# AD_Test.net
KiCad netlist of a schematic drawn in EAGLE
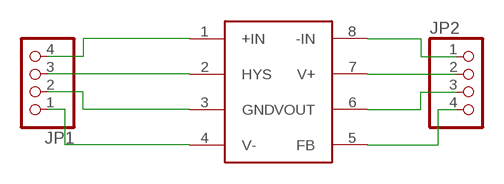
[diagram p0: schematic, sheet 1]

(export (version "E")
  (design (tool "Eeschema 10.0.6"))
  (components
    (comp (ref "JP1")
      (value "PINHD-1X4")
      (footprint "eagle-import:1X04")
      (libsource (lib "eagle-import") (part "PINHD-1X4"))
    )
    (comp (ref "JP2")
      (value "PINHD-1X4")
      (footprint "eagle-import:1X04")
      (libsource (lib "eagle-import") (part "PINHD-1X4"))
    )
    (comp (ref "U$1")
      (value "AD597ARZ")
      (footprint "eagle-import:SO8")
      (libsource (lib "eagle-import") (part "AD597ARZ"))
    )
  )
  (nets
    (net (code "1") (name "Net-(U$1-+IN)") (class "Default")
      (node (ref "JP1") (pin "4") (pinfunction "4_4") (pintype "passive"))
      (node (ref "U$1") (pin "1") (pinfunction "+IN_1") (pintype "bidirectional"))
    )
    (net (code "2") (name "Net-(U$1--IN)") (class "Default")
      (node (ref "JP2") (pin "1") (pinfunction "1_1") (pintype "passive"))
      (node (ref "U$1") (pin "8") (pinfunction "-IN_8") (pintype "bidirectional"))
    )
    (net (code "3") (name "Net-(U$1-FB)") (class "Default")
      (node (ref "JP2") (pin "4") (pinfunction "4_4") (pintype "passive"))
      (node (ref "U$1") (pin "5") (pinfunction "FB_5") (pintype "bidirectional"))
    )
    (net (code "4") (name "Net-(U$1-GND)") (class "Default")
      (node (ref "JP1") (pin "2") (pinfunction "2_2") (pintype "passive"))
      (node (ref "U$1") (pin "3") (pinfunction "GND_3") (pintype "bidirectional"))
    )
    (net (code "5") (name "Net-(U$1-HYS)") (class "Default")
      (node (ref "JP1") (pin "3") (pinfunction "3_3") (pintype "passive"))
      (node (ref "U$1") (pin "2") (pinfunction "HYS_2") (pintype "bidirectional"))
    )
    (net (code "6") (name "Net-(U$1-V+)") (class "Default")
      (node (ref "JP2") (pin "2") (pinfunction "2_2") (pintype "passive"))
      (node (ref "U$1") (pin "7") (pinfunction "V+_7") (pintype "bidirectional"))
    )
    (net (code "7") (name "Net-(U$1-V-)") (class "Default")
      (node (ref "JP1") (pin "1") (pinfunction "1_1") (pintype "passive"))
      (node (ref "U$1") (pin "4") (pinfunction "V-_4") (pintype "bidirectional"))
    )
    (net (code "8") (name "Net-(U$1-VOUT)") (class "Default")
      (node (ref "JP2") (pin "3") (pinfunction "3_3") (pintype "passive"))
      (node (ref "U$1") (pin "6") (pinfunction "VOUT_6") (pintype "bidirectional"))
    )
  )
)
